# MCU.net
KiCad netlist of a schematic drawn in Altium Designer
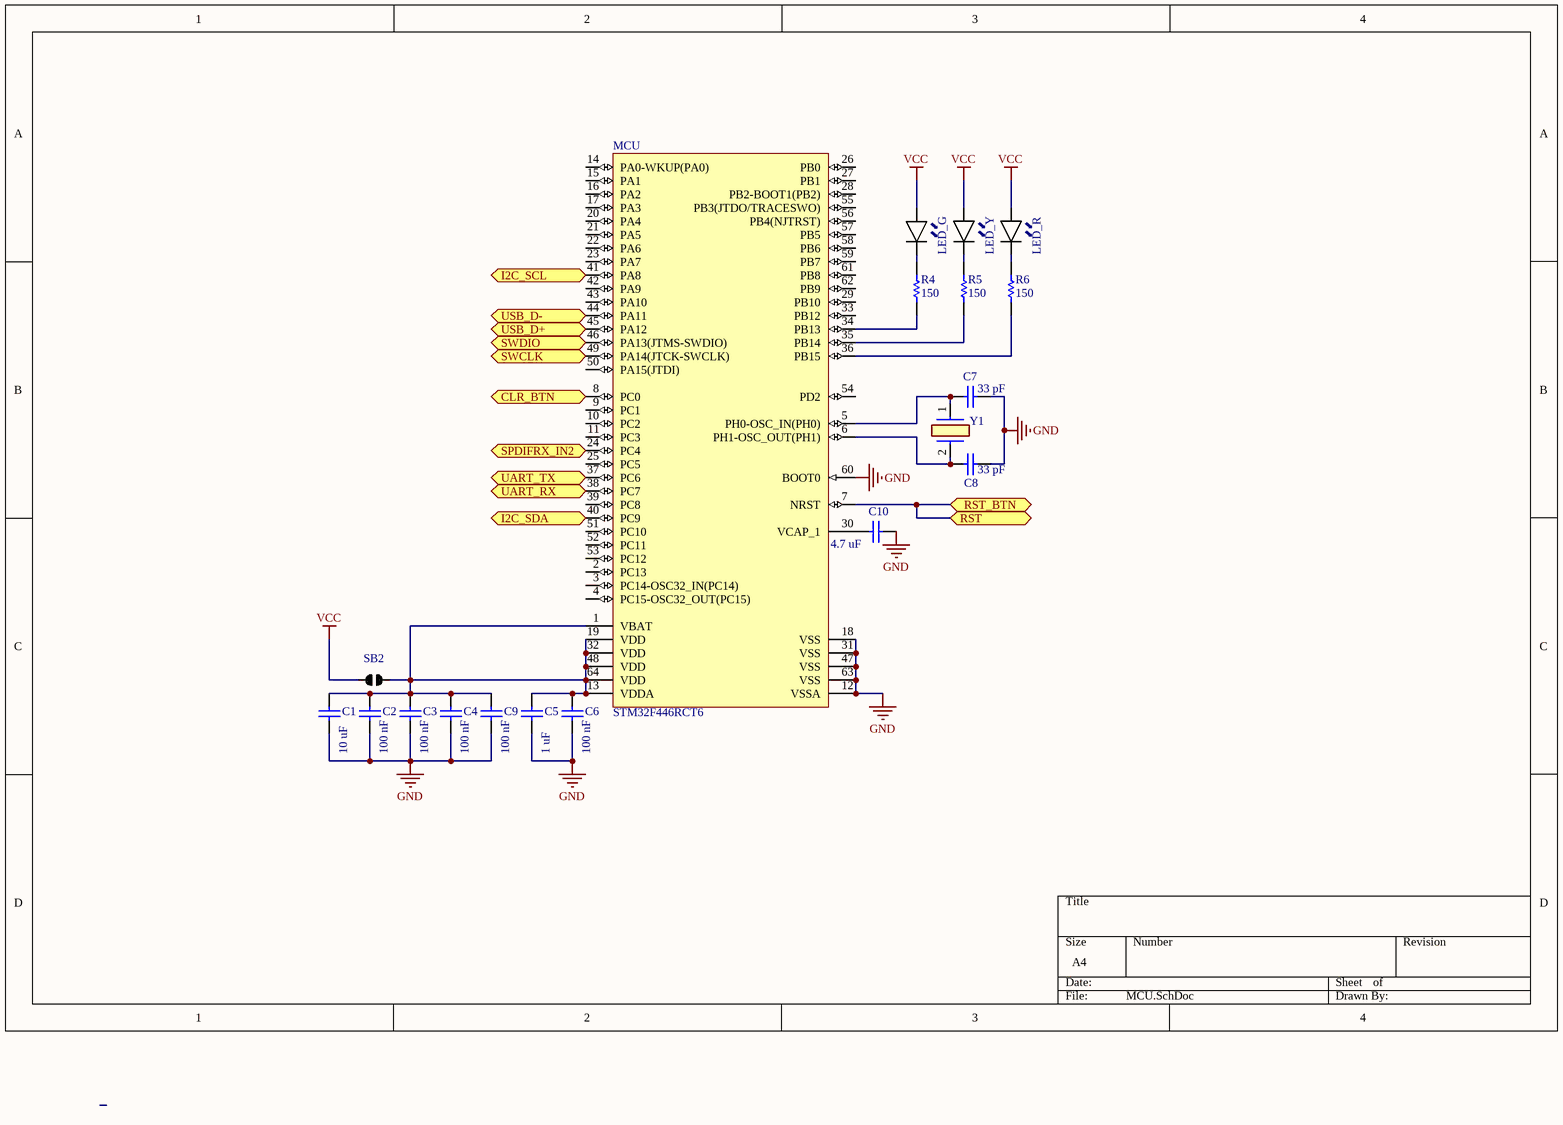
[diagram p0: MCU.SchDoc]

(export (version "E")
  (design (tool "Eeschema 10.0.6"))
  (components
    (comp (ref "C1")
      (value "10 uF")
      (footprint "J1-0603")
      (description "Capacitor")
      (fields (field (name "Comment") "C19702") (field (name "PUBLISHER") "Altium Limited"))
      (libsource (lib "Miscellaneous Devices") (part "Cap"))
    )
    (comp (ref "C2")
      (value "100 nF")
      (footprint "0402")
      (description "Capacitor")
      (fields (field (name "Comment") "C1525") (field (name "PUBLISHER") "Altium Limited"))
      (libsource (lib "Miscellaneous Devices") (part "Cap"))
    )
    (comp (ref "C3")
      (value "100 nF")
      (footprint "0402")
      (description "Capacitor")
      (fields (field (name "Comment") "C1525") (field (name "PUBLISHER") "Altium Limited"))
      (libsource (lib "Miscellaneous Devices") (part "Cap"))
    )
    (comp (ref "C4")
      (value "100 nF")
      (footprint "0402")
      (description "Capacitor")
      (fields (field (name "Comment") "C1525") (field (name "PUBLISHER") "Altium Limited"))
      (libsource (lib "Miscellaneous Devices") (part "Cap"))
    )
    (comp (ref "C5")
      (value "1 uF")
      (footprint "J1-0603")
      (description "Capacitor")
      (fields (field (name "Comment") "C15849") (field (name "PUBLISHER") "Altium Limited"))
      (libsource (lib "Miscellaneous Devices") (part "Cap"))
    )
    (comp (ref "C6")
      (value "100 nF")
      (footprint "0402")
      (description "Capacitor")
      (fields (field (name "Comment") "C1525") (field (name "PUBLISHER") "Altium Limited"))
      (libsource (lib "Miscellaneous Devices") (part "Cap"))
    )
    (comp (ref "C7")
      (value "33 pF")
      (footprint "0402")
      (description "Capacitor")
      (fields (field (name "Comment") "C1562") (field (name "PUBLISHER") "Altium Limited"))
      (libsource (lib "Miscellaneous Devices") (part "Cap"))
    )
    (comp (ref "C8")
      (value "33 pF")
      (footprint "0402")
      (description "Capacitor")
      (fields (field (name "Comment") "C1562") (field (name "PUBLISHER") "Altium Limited"))
      (libsource (lib "Miscellaneous Devices") (part "Cap"))
    )
    (comp (ref "C9")
      (value "100 nF")
      (footprint "0402")
      (description "Capacitor")
      (fields (field (name "Comment") "C1525") (field (name "PUBLISHER") "Altium Limited"))
      (libsource (lib "Miscellaneous Devices") (part "Cap"))
    )
    (comp (ref "C10")
      (value "4.7 uF")
      (footprint "J1-0603")
      (description "Capacitor")
      (fields (field (name "Comment") "C19666") (field (name "PUBLISHER") "Altium Limited"))
      (libsource (lib "Miscellaneous Devices") (part "Cap"))
    )
    (comp (ref "LED_G")
      (value "fucking led maat hoe moeilijk ist kutprogram")
      (footprint "LED_SSL-LX4673GD-LA20")
      (description "DNP")
      (libsource (lib "Schlib1") (part "fucking led maat hoe moeilijk ist kutprogram"))
    )
    (comp (ref "LED_R")
      (value "fucking led maat hoe moeilijk ist kutprogram")
      (footprint "LED_SSL-LX4673GD-LA20")
      (description "DNP")
      (libsource (lib "Schlib1") (part "fucking led maat hoe moeilijk ist kutprogram"))
    )
    (comp (ref "LED_Y")
      (value "fucking led maat hoe moeilijk ist kutprogram")
      (footprint "LED_SSL-LX4673GD-LA20")
      (description "DNP")
      (libsource (lib "Schlib1") (part "fucking led maat hoe moeilijk ist kutprogram"))
    )
    (comp (ref "MCU")
      (value "STM32F446RCT6")
      (footprint "STM-LQFP64_L")
      (libsource (lib "Altium Content Vault") (part "MC-ARM-STM32F446-LQFP64"))
    )
    (comp (ref "R4")
      (value "150")
      (footprint "J1-0603")
      (description "C22808")
      (fields (field (name "PUBLISHER") "Altium Limited"))
      (libsource (lib "Miscellaneous Devices") (part "Res1"))
    )
    (comp (ref "R5")
      (value "150")
      (footprint "J1-0603")
      (description "C22808")
      (fields (field (name "PUBLISHER") "Altium Limited"))
      (libsource (lib "Miscellaneous Devices") (part "Res1"))
    )
    (comp (ref "R6")
      (value "150")
      (footprint "J1-0603")
      (description "C22808")
      (fields (field (name "PUBLISHER") "Altium Limited"))
      (libsource (lib "Miscellaneous Devices") (part "Res1"))
    )
    (comp (ref "SB2")
      (value "Solder Bridge")
      (footprint "Solder Bridge")
      (description "DNP")
      (libsource (lib "schematic") (part "Solder Bridge"))
    )
    (comp (ref "Y1")
      (value "X50328MSB2GI")
      (footprint "SamacSys:RESC5032X135N")
      (description "C115962")
      (libsource (lib "*") (part "X50328MSB2GI"))
    )
  )
  (nets
    (net (code "2") (name "/CLR_BTN") (class "Default")
      (node (ref "MCU") (pin "8") (pinfunction "PC0_8") (pintype "bidirectional"))
    )
    (net (code "3") (name "/I2C_SCL") (class "Default")
      (node (ref "MCU") (pin "41") (pinfunction "PA8_41") (pintype "bidirectional"))
    )
    (net (code "4") (name "/I2C_SDA") (class "Default")
      (node (ref "MCU") (pin "40") (pinfunction "PC9_40") (pintype "bidirectional"))
    )
    (net (code "5") (name "/RST") (class "Default")
      (node (ref "MCU") (pin "7") (pinfunction "NRST_7") (pintype "bidirectional"))
    )
    (net (code "6") (name "/SPDIFRX_IN2") (class "Default")
      (node (ref "MCU") (pin "24") (pinfunction "PC4_24") (pintype "bidirectional"))
    )
    (net (code "7") (name "/SWCLK") (class "Default")
      (node (ref "MCU") (pin "49") (pinfunction "PA14(JTCK-SWCLK)_49") (pintype "bidirectional"))
    )
    (net (code "8") (name "/SWDIO") (class "Default")
      (node (ref "MCU") (pin "46") (pinfunction "PA13(JTMS-SWDIO)_46") (pintype "bidirectional"))
    )
    (net (code "9") (name "/UART_RX") (class "Default")
      (node (ref "MCU") (pin "38") (pinfunction "PC7_38") (pintype "bidirectional"))
    )
    (net (code "10") (name "/UART_TX") (class "Default")
      (node (ref "MCU") (pin "37") (pinfunction "PC6_37") (pintype "bidirectional"))
    )
    (net (code "11") (name "/USB_D+") (class "Default")
      (node (ref "MCU") (pin "45") (pinfunction "PA12_45") (pintype "bidirectional"))
    )
    (net (code "12") (name "/USB_D-") (class "Default")
      (node (ref "MCU") (pin "44") (pinfunction "PA11_44") (pintype "bidirectional"))
    )
    (net (code "13") (name "GND") (class "Default")
      (node (ref "C1") (pin "1") (pinfunction "1_1") (pintype "passive"))
      (node (ref "C10") (pin "2") (pinfunction "2_2") (pintype "passive"))
      (node (ref "C2") (pin "1") (pinfunction "1_1") (pintype "passive"))
      (node (ref "C3") (pin "1") (pinfunction "1_1") (pintype "passive"))
      (node (ref "C4") (pin "1") (pinfunction "1_1") (pintype "passive"))
      (node (ref "C5") (pin "1") (pinfunction "1_1") (pintype "passive"))
      (node (ref "C6") (pin "1") (pinfunction "1_1") (pintype "passive"))
      (node (ref "C7") (pin "2") (pinfunction "2_2") (pintype "passive"))
      (node (ref "C8") (pin "2") (pinfunction "2_2") (pintype "passive"))
      (node (ref "C9") (pin "1") (pinfunction "1_1") (pintype "passive"))
      (node (ref "MCU") (pin "12") (pinfunction "VSSA_12") (pintype "power_in"))
      (node (ref "MCU") (pin "18") (pinfunction "VSS_18") (pintype "power_in"))
      (node (ref "MCU") (pin "31") (pinfunction "VSS_31") (pintype "power_in"))
      (node (ref "MCU") (pin "47") (pinfunction "VSS_47") (pintype "power_in"))
      (node (ref "MCU") (pin "60") (pinfunction "BOOT0_60") (pintype "input"))
      (node (ref "MCU") (pin "63") (pinfunction "VSS_63") (pintype "power_in"))
    )
    (net (code "14") (name "Net-(LED_G-Pad1)") (class "Default")
      (node (ref "LED_G") (pin "1") (pinfunction "1_1") (pintype "passive"))
      (node (ref "R4") (pin "1") (pinfunction "1_1") (pintype "passive"))
    )
    (net (code "15") (name "Net-(LED_R-Pad1)") (class "Default")
      (node (ref "LED_R") (pin "1") (pinfunction "1_1") (pintype "passive"))
      (node (ref "R6") (pin "1") (pinfunction "1_1") (pintype "passive"))
    )
    (net (code "16") (name "Net-(LED_Y-Pad1)") (class "Default")
      (node (ref "LED_Y") (pin "1") (pinfunction "1_1") (pintype "passive"))
      (node (ref "R5") (pin "1") (pinfunction "1_1") (pintype "passive"))
    )
    (net (code "17") (name "Net-(MCU-PB13)") (class "Default")
      (node (ref "MCU") (pin "34") (pinfunction "PB13_34") (pintype "bidirectional"))
      (node (ref "R4") (pin "2") (pinfunction "2_2") (pintype "passive"))
    )
    (net (code "18") (name "Net-(MCU-PB14)") (class "Default")
      (node (ref "MCU") (pin "35") (pinfunction "PB14_35") (pintype "bidirectional"))
      (node (ref "R5") (pin "2") (pinfunction "2_2") (pintype "passive"))
    )
    (net (code "19") (name "Net-(MCU-PB15)") (class "Default")
      (node (ref "MCU") (pin "36") (pinfunction "PB15_36") (pintype "bidirectional"))
      (node (ref "R6") (pin "2") (pinfunction "2_2") (pintype "passive"))
    )
    (net (code "20") (name "Net-(MCU-PH0-OSC_IN(PH0))") (class "Default")
      (node (ref "C7") (pin "1") (pinfunction "1_1") (pintype "passive"))
      (node (ref "MCU") (pin "5") (pinfunction "PH0-OSC_IN(PH0)_5") (pintype "bidirectional"))
      (node (ref "Y1") (pin "1") (pinfunction "1_1") (pintype "passive"))
    )
    (net (code "21") (name "Net-(MCU-PH1-OSC_OUT(PH1))") (class "Default")
      (node (ref "C8") (pin "1") (pinfunction "1_1") (pintype "passive"))
      (node (ref "MCU") (pin "6") (pinfunction "PH1-OSC_OUT(PH1)_6") (pintype "bidirectional"))
      (node (ref "Y1") (pin "2") (pinfunction "2_2") (pintype "passive"))
    )
    (net (code "22") (name "Net-(MCU-VBAT)") (class "Default")
      (node (ref "C1") (pin "2") (pinfunction "2_2") (pintype "passive"))
      (node (ref "C2") (pin "2") (pinfunction "2_2") (pintype "passive"))
      (node (ref "C3") (pin "2") (pinfunction "2_2") (pintype "passive"))
      (node (ref "C4") (pin "2") (pinfunction "2_2") (pintype "passive"))
      (node (ref "C5") (pin "2") (pinfunction "2_2") (pintype "passive"))
      (node (ref "C6") (pin "2") (pinfunction "2_2") (pintype "passive"))
      (node (ref "C9") (pin "2") (pinfunction "2_2") (pintype "passive"))
      (node (ref "MCU") (pin "1") (pinfunction "VBAT_1") (pintype "power_in"))
      (node (ref "MCU") (pin "13") (pinfunction "VDDA_13") (pintype "power_in"))
      (node (ref "MCU") (pin "19") (pinfunction "VDD_19") (pintype "power_in"))
      (node (ref "MCU") (pin "32") (pinfunction "VDD_32") (pintype "power_in"))
      (node (ref "MCU") (pin "48") (pinfunction "VDD_48") (pintype "power_in"))
      (node (ref "MCU") (pin "64") (pinfunction "VDD_64") (pintype "power_in"))
      (node (ref "SB2") (pin "2") (pinfunction "3_2") (pintype "passive"))
    )
    (net (code "23") (name "Net-(MCU-VCAP_1)") (class "Default")
      (node (ref "C10") (pin "1") (pinfunction "1_1") (pintype "passive"))
      (node (ref "MCU") (pin "30") (pinfunction "VCAP_1_30") (pintype "passive"))
    )
    (net (code "24") (name "VCC") (class "Default")
      (node (ref "LED_G") (pin "2") (pinfunction "2_2") (pintype "passive"))
      (node (ref "LED_R") (pin "2") (pinfunction "2_2") (pintype "passive"))
      (node (ref "LED_Y") (pin "2") (pinfunction "2_2") (pintype "passive"))
      (node (ref "SB2") (pin "1") (pinfunction "3_1") (pintype "passive"))
    )
    (net (code "25") (name "unconnected-(MCU-PA0-WKUP(PA0)-Pad14)") (class "Default")
      (node (ref "MCU") (pin "14") (pinfunction "PA0-WKUP(PA0)_14") (pintype "bidirectional"))
    )
    (net (code "26") (name "unconnected-(MCU-PA1-Pad15)") (class "Default")
      (node (ref "MCU") (pin "15") (pinfunction "PA1_15") (pintype "bidirectional"))
    )
    (net (code "27") (name "unconnected-(MCU-PA2-Pad16)") (class "Default")
      (node (ref "MCU") (pin "16") (pinfunction "PA2_16") (pintype "bidirectional"))
    )
    (net (code "28") (name "unconnected-(MCU-PA3-Pad17)") (class "Default")
      (node (ref "MCU") (pin "17") (pinfunction "PA3_17") (pintype "bidirectional"))
    )
    (net (code "29") (name "unconnected-(MCU-PA4-Pad20)") (class "Default")
      (node (ref "MCU") (pin "20") (pinfunction "PA4_20") (pintype "bidirectional"))
    )
    (net (code "30") (name "unconnected-(MCU-PA5-Pad21)") (class "Default")
      (node (ref "MCU") (pin "21") (pinfunction "PA5_21") (pintype "bidirectional"))
    )
    (net (code "31") (name "unconnected-(MCU-PA6-Pad22)") (class "Default")
      (node (ref "MCU") (pin "22") (pinfunction "PA6_22") (pintype "bidirectional"))
    )
    (net (code "32") (name "unconnected-(MCU-PA7-Pad23)") (class "Default")
      (node (ref "MCU") (pin "23") (pinfunction "PA7_23") (pintype "bidirectional"))
    )
    (net (code "33") (name "unconnected-(MCU-PA9-Pad42)") (class "Default")
      (node (ref "MCU") (pin "42") (pinfunction "PA9_42") (pintype "bidirectional"))
    )
    (net (code "34") (name "unconnected-(MCU-PA10-Pad43)") (class "Default")
      (node (ref "MCU") (pin "43") (pinfunction "PA10_43") (pintype "bidirectional"))
    )
    (net (code "35") (name "unconnected-(MCU-PA15(JTDI)-Pad50)") (class "Default")
      (node (ref "MCU") (pin "50") (pinfunction "PA15(JTDI)_50") (pintype "bidirectional"))
    )
    (net (code "36") (name "unconnected-(MCU-PB0-Pad26)") (class "Default")
      (node (ref "MCU") (pin "26") (pinfunction "PB0_26") (pintype "bidirectional"))
    )
    (net (code "37") (name "unconnected-(MCU-PB1-Pad27)") (class "Default")
      (node (ref "MCU") (pin "27") (pinfunction "PB1_27") (pintype "bidirectional"))
    )
    (net (code "38") (name "unconnected-(MCU-PB2-BOOT1(PB2)-Pad28)") (class "Default")
      (node (ref "MCU") (pin "28") (pinfunction "PB2-BOOT1(PB2)_28") (pintype "bidirectional"))
    )
    (net (code "39") (name "unconnected-(MCU-PB3(JTDO{slash}TRACESWO)-Pad55)") (class "Default")
      (node (ref "MCU") (pin "55") (pinfunction "PB3(JTDO/TRACESWO)_55") (pintype "bidirectional"))
    )
    (net (code "40") (name "unconnected-(MCU-PB4(NJTRST)-Pad56)") (class "Default")
      (node (ref "MCU") (pin "56") (pinfunction "PB4(NJTRST)_56") (pintype "bidirectional"))
    )
    (net (code "41") (name "unconnected-(MCU-PB5-Pad57)") (class "Default")
      (node (ref "MCU") (pin "57") (pinfunction "PB5_57") (pintype "bidirectional"))
    )
    (net (code "42") (name "unconnected-(MCU-PB6-Pad58)") (class "Default")
      (node (ref "MCU") (pin "58") (pinfunction "PB6_58") (pintype "bidirectional"))
    )
    (net (code "43") (name "unconnected-(MCU-PB7-Pad59)") (class "Default")
      (node (ref "MCU") (pin "59") (pinfunction "PB7_59") (pintype "bidirectional"))
    )
    (net (code "44") (name "unconnected-(MCU-PB8-Pad61)") (class "Default")
      (node (ref "MCU") (pin "61") (pinfunction "PB8_61") (pintype "bidirectional"))
    )
    (net (code "45") (name "unconnected-(MCU-PB9-Pad62)") (class "Default")
      (node (ref "MCU") (pin "62") (pinfunction "PB9_62") (pintype "bidirectional"))
    )
    (net (code "46") (name "unconnected-(MCU-PB10-Pad29)") (class "Default")
      (node (ref "MCU") (pin "29") (pinfunction "PB10_29") (pintype "bidirectional"))
    )
    (net (code "47") (name "unconnected-(MCU-PB12-Pad33)") (class "Default")
      (node (ref "MCU") (pin "33") (pinfunction "PB12_33") (pintype "bidirectional"))
    )
    (net (code "48") (name "unconnected-(MCU-PC1-Pad9)") (class "Default")
      (node (ref "MCU") (pin "9") (pinfunction "PC1_9") (pintype "bidirectional"))
    )
    (net (code "49") (name "unconnected-(MCU-PC2-Pad10)") (class "Default")
      (node (ref "MCU") (pin "10") (pinfunction "PC2_10") (pintype "bidirectional"))
    )
    (net (code "50") (name "unconnected-(MCU-PC3-Pad11)") (class "Default")
      (node (ref "MCU") (pin "11") (pinfunction "PC3_11") (pintype "bidirectional"))
    )
    (net (code "51") (name "unconnected-(MCU-PC5-Pad25)") (class "Default")
      (node (ref "MCU") (pin "25") (pinfunction "PC5_25") (pintype "bidirectional"))
    )
    (net (code "52") (name "unconnected-(MCU-PC8-Pad39)") (class "Default")
      (node (ref "MCU") (pin "39") (pinfunction "PC8_39") (pintype "bidirectional"))
    )
    (net (code "53") (name "unconnected-(MCU-PC10-Pad51)") (class "Default")
      (node (ref "MCU") (pin "51") (pinfunction "PC10_51") (pintype "bidirectional"))
    )
    (net (code "54") (name "unconnected-(MCU-PC11-Pad52)") (class "Default")
      (node (ref "MCU") (pin "52") (pinfunction "PC11_52") (pintype "bidirectional"))
    )
    (net (code "55") (name "unconnected-(MCU-PC12-Pad53)") (class "Default")
      (node (ref "MCU") (pin "53") (pinfunction "PC12_53") (pintype "bidirectional"))
    )
    (net (code "56") (name "unconnected-(MCU-PC13-Pad2)") (class "Default")
      (node (ref "MCU") (pin "2") (pinfunction "PC13_2") (pintype "bidirectional"))
    )
    (net (code "57") (name "unconnected-(MCU-PC14-OSC32_IN(PC14)-Pad3)") (class "Default")
      (node (ref "MCU") (pin "3") (pinfunction "PC14-OSC32_IN(PC14)_3") (pintype "bidirectional"))
    )
    (net (code "58") (name "unconnected-(MCU-PC15-OSC32_OUT(PC15)-Pad4)") (class "Default")
      (node (ref "MCU") (pin "4") (pinfunction "PC15-OSC32_OUT(PC15)_4") (pintype "bidirectional"))
    )
    (net (code "59") (name "unconnected-(MCU-PD2-Pad54)") (class "Default")
      (node (ref "MCU") (pin "54") (pinfunction "PD2_54") (pintype "bidirectional"))
    )
  )
)
